# MCU.net
KiCad netlist of a schematic drawn in Altium Designer
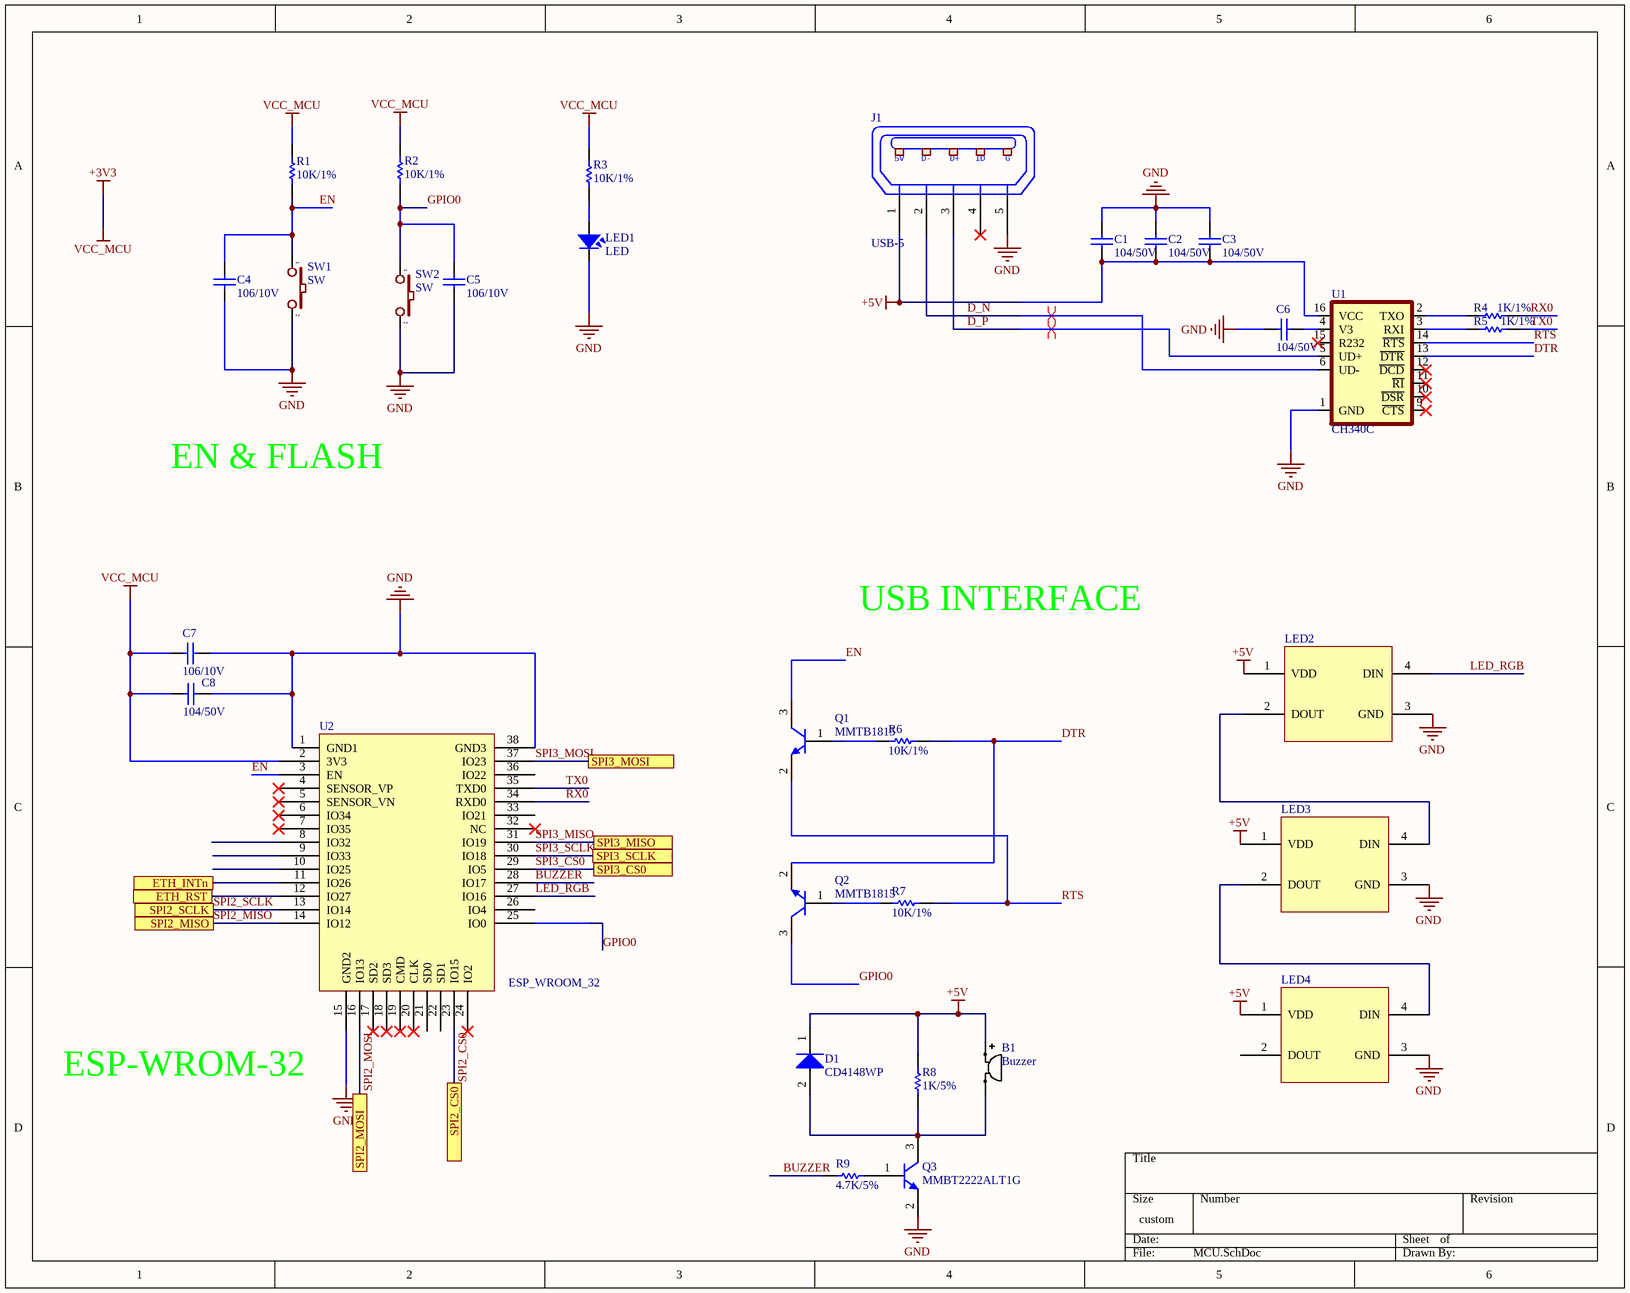
[diagram p0: MCU.SchDoc]

(export (version "E")
  (design (tool "Eeschema 10.0.6"))
  (components
    (comp (ref "B1")
      (value "Buzzer")
      (footprint "PS1240P02BT")
      (description "Audio Indicators & Alerts Round 12.2mmx6.5mm 4kHz Vin=3V")
      (fields
        (field (name "PARTNUMBER") "PS1240P02BT")
        (field (name "BSH PARTNUMBER") "New part")
        (field (name "CREATOR") "NamNHc")
      )
      (libsource (lib "library-SH") (part "BUZZER"))
    )
    (comp (ref "C1")
      (value "104/50V")
      (footprint "C0603-B")
      (description "100nF ±10% 50V X7R 0603 Multilayer Ceramic Capacitors MLCC - SMD/SMT RoHS")
      (fields
        (field (name "PARTNUMBER") "CL10B104KB8NNNC")
        (field (name "BSH PARTNUMBER") "C1591")
        (field (name "CREATOR") "Digo")
      )
      (libsource (lib "library-SH") (part "CAP"))
    )
    (comp (ref "C2")
      (value "104/50V")
      (footprint "C0603-B")
      (description "100nF ±10% 50V X7R 0603 Multilayer Ceramic Capacitors MLCC - SMD/SMT RoHS")
      (fields
        (field (name "PARTNUMBER") "CL10B104KB8NNNC")
        (field (name "BSH PARTNUMBER") "C1591")
        (field (name "CREATOR") "Digo")
      )
      (libsource (lib "library-SH") (part "CAP"))
    )
    (comp (ref "C3")
      (value "104/50V")
      (footprint "C0603-B")
      (description "100nF ±10% 50V X7R 0603 Multilayer Ceramic Capacitors MLCC - SMD/SMT RoHS")
      (fields
        (field (name "PARTNUMBER") "CL10B104KB8NNNC")
        (field (name "BSH PARTNUMBER") "C1591")
        (field (name "CREATOR") "Digo")
      )
      (libsource (lib "library-SH") (part "CAP"))
    )
    (comp (ref "C4")
      (value "106/10V")
      (footprint "C0603-B")
      (description "10uF ±10% 10V X5R 0603 Multilayer Ceramic Capacitors MLCC - SMD/SMT RoHS")
      (fields
        (field (name "PARTNUMBER") "CL10A106KP8NNNC")
        (field (name "BSH PARTNUMBER") "C19702")
        (field (name "CREATOR") "Digo")
      )
      (libsource (lib "library-SH") (part "CAP"))
    )
    (comp (ref "C5")
      (value "106/10V")
      (footprint "C0603-B")
      (description "10uF ±10% 10V X5R 0603 Multilayer Ceramic Capacitors MLCC - SMD/SMT RoHS")
      (fields
        (field (name "PARTNUMBER") "CL10A106KP8NNNC")
        (field (name "BSH PARTNUMBER") "C19702")
        (field (name "CREATOR") "Digo")
      )
      (libsource (lib "library-SH") (part "CAP"))
    )
    (comp (ref "C6")
      (value "104/50V")
      (footprint "C0603-B")
      (description "100nF ±10% 50V X7R 0603 Multilayer Ceramic Capacitors MLCC - SMD/SMT RoHS")
      (fields
        (field (name "PARTNUMBER") "CL10B104KB8NNNC")
        (field (name "BSH PARTNUMBER") "C1591")
        (field (name "CREATOR") "Digo")
      )
      (libsource (lib "library-SH") (part "CAP"))
    )
    (comp (ref "C7")
      (value "106/10V")
      (footprint "C0603-B")
      (description "10uF ±10% 10V X5R 0603 Multilayer Ceramic Capacitors MLCC - SMD/SMT RoHS")
      (fields
        (field (name "PARTNUMBER") "CL10A106KP8NNNC")
        (field (name "BSH PARTNUMBER") "C19702")
        (field (name "CREATOR") "Digo")
      )
      (libsource (lib "library-SH") (part "CAP"))
    )
    (comp (ref "C8")
      (value "104/50V")
      (footprint "C0603-B")
      (description "100nF ±10% 50V X7R 0603 Multilayer Ceramic Capacitors MLCC - SMD/SMT RoHS")
      (fields
        (field (name "PARTNUMBER") "CL10B104KB8NNNC")
        (field (name "BSH PARTNUMBER") "C1591")
        (field (name "CREATOR") "Digo")
      )
      (libsource (lib "library-SH") (part "CAP"))
    )
    (comp (ref "D1")
      (value "CD4148WP")
      (footprint "D1206-C")
      (description "DIO D1206 150mA 75V Switching Chip Diode")
      (fields (field (name "BSH PARTNUMBER") "D-CD4148WP") (field (name "CREATOR") "ChienNQ"))
      (libsource (lib "library-SH") (part "DIOT"))
    )
    (comp (ref "J1")
      (value "USB-5")
      (footprint "USB-M1")
      (fields
        (field (name "MANUFACTURER") "FCI")
        (field (name "MANUFACTURER PART NUMBER") "10118193-0001LF")
        (field (name ".CREATOR") "MM")
        (field (name ".CHECKED PCB") "RF")
        (field (name ".CHECKED SCH") "MM")
      )
      (libsource (lib "My Library") (part "USB-5"))
    )
    (comp (ref "LED1")
      (value "LED")
      (footprint "LED-0805-Red")
      (description "LED Single colour Green and Red")
      (libsource (lib "HS_Lib") (part "LED"))
    )
    (comp (ref "LED2")
      (value "RGB 4 Pin WS2812B")
      (footprint "WS2812B")
      (description "Intelligent control LED\r\nintegrated light source")
      (libsource (lib "My Library") (part "WS2812B"))
    )
    (comp (ref "LED3")
      (value "RGB 4 Pin WS2812B")
      (footprint "WS2812B")
      (description "Intelligent control LED\r\nintegrated light source")
      (libsource (lib "My Library") (part "WS2812B"))
    )
    (comp (ref "LED4")
      (value "RGB 4 Pin WS2812B")
      (footprint "WS2812B")
      (description "Intelligent control LED\r\nintegrated light source")
      (libsource (lib "My Library") (part "WS2812B"))
    )
    (comp (ref "Q1")
      (value "MMTB1815")
      (footprint "SOT23-321-C")
      (description "Transistor NPN SOT23 MMTB1815 Pitch_0.90 mm 2.92x2.00x1.11 mm")
      (fields (field (name "BSH PARTNUMBER") "Q-MMBT1815-TP") (field (name "CREATOR") "DucNTc"))
      (libsource (lib "library-SH") (part "Transistors-NPN"))
    )
    (comp (ref "Q2")
      (value "MMTB1815")
      (footprint "SOT23-321-C")
      (description "Transistor NPN SOT23 MMTB1815 Pitch_0.90 mm 2.92x2.00x1.11 mm")
      (fields (field (name "BSH PARTNUMBER") "Q-MMBT1815-TP") (field (name "CREATOR") "DucNTc"))
      (libsource (lib "library-SH") (part "Transistors-NPN"))
    )
    (comp (ref "Q3")
      (value "MMBT2222ALT1G")
      (footprint "SOT23-321-B")
      (description "Transistor NPN SOT23 MMBT2222A Pitch_0.90 mm 2.92x2.00x1.11mm")
      (fields (field (name "BSH PARTNUMBER") "Q-MMBT2222A") (field (name "CREATOR") "SmartDevice"))
      (libsource (lib "library-SH") (part "Transistors-NPN"))
    )
    (comp (ref "R1")
      (value "10K/1%")
      (footprint "R0603-B")
      (description "RES 0603 10K 1% 100mW")
      (fields
        (field (name "PARTNUMBER") "RC0603FR-0710KL")
        (field (name "BSH PARTNUMBER") "C98220")
        (field (name "CREATOR") "Digo")
      )
      (libsource (lib "library-SH") (part "RES"))
    )
    (comp (ref "R2")
      (value "10K/1%")
      (footprint "R0603-B")
      (description "RES 0603 10K 1% 100mW")
      (fields
        (field (name "PARTNUMBER") "RC0603FR-0710KL")
        (field (name "BSH PARTNUMBER") "C98220")
        (field (name "CREATOR") "Digo")
      )
      (libsource (lib "library-SH") (part "RES"))
    )
    (comp (ref "R3")
      (value "10K/1%")
      (footprint "R0603-B")
      (description "RES 0603 10K 1% 100mW")
      (fields
        (field (name "PARTNUMBER") "RC0603FR-0710KL")
        (field (name "BSH PARTNUMBER") "C98220")
        (field (name "CREATOR") "Digo")
      )
      (libsource (lib "library-SH") (part "RES"))
    )
    (comp (ref "R4")
      (value "1K/1%")
      (footprint "R0603-B")
      (description "RES 0603 1K 1% 100mW")
      (fields
        (field (name "PARTNUMBER") "RC0603FR-071KL")
        (field (name "BSH PARTNUMBER") "R-1k-0603-1")
        (field (name "CREATOR") "SmartDevice")
      )
      (libsource (lib "library-SH") (part "RES"))
    )
    (comp (ref "R5")
      (value "1K/1%")
      (footprint "R0603-B")
      (description "RES 0603 1K 1% 100mW")
      (fields
        (field (name "PARTNUMBER") "RC0603FR-071KL")
        (field (name "BSH PARTNUMBER") "R-1k-0603-1")
        (field (name "CREATOR") "SmartDevice")
      )
      (libsource (lib "library-SH") (part "RES"))
    )
    (comp (ref "R6")
      (value "10K/1%")
      (footprint "R0603-B")
      (description "RES 0603 10K 1% 100mW")
      (fields
        (field (name "PARTNUMBER") "RC0603FR-0710KL")
        (field (name "BSH PARTNUMBER") "C98220")
        (field (name "CREATOR") "Digo")
      )
      (libsource (lib "library-SH") (part "RES"))
    )
    (comp (ref "R7")
      (value "10K/1%")
      (footprint "R0603-B")
      (description "RES 0603 10K 1% 100mW")
      (fields
        (field (name "PARTNUMBER") "RC0603FR-0710KL")
        (field (name "BSH PARTNUMBER") "C98220")
        (field (name "CREATOR") "Digo")
      )
      (libsource (lib "library-SH") (part "RES"))
    )
    (comp (ref "R8")
      (value "1K/5%")
      (footprint "R0603-B")
      (description "RES 0603 1K 5% 100mW")
      (fields
        (field (name "PARTNUMBER") "RC0603JR-071KL")
        (field (name "BSH PARTNUMBER") "R-1K-0603-5")
        (field (name "CREATOR") "SmartDevice")
      )
      (libsource (lib "library-SH") (part "RES"))
    )
    (comp (ref "R9")
      (value "4.7K/5%")
      (footprint "R0603-B")
      (description "RES 0603 4K7 5% 100mW")
      (fields
        (field (name "PARTNUMBER") "RC0603JR-074K7L")
        (field (name "BSH PARTNUMBER") "R-4K7-0603-5")
        (field (name "CREATOR") "SmartDevice")
      )
      (libsource (lib "library-SH") (part "RES"))
    )
    (comp (ref "SW1")
      (value "SW")
      (footprint "SW2 - 3x4x2.5")
      (description "Switch button 2 pin")
      (libsource (lib "My Library") (part "SW2"))
    )
    (comp (ref "SW2")
      (value "SW")
      (footprint "SW2 - 3x4x2.5")
      (description "Switch button 2 pin")
      (libsource (lib "My Library") (part "SW2"))
    )
    (comp (ref "U1")
      (value "CH340C")
      (footprint "SO016")
      (description "USB to serial chip CH340")
      (fields (field (name "MF") "WCH"))
      (libsource (lib "HS_Lib") (part "CH340C"))
    )
    (comp (ref "U2")
      (value "ESP_WROOM_32")
      (footprint "ESP32_WROOM_32")
      (fields
        (field (name "MANUFACTURER") "Espressif Systems")
        (field (name "MANUFACTURER PART NUMBER") "ESP32-WROOM-32E(4MBHIGHTEMP)")
      )
      (libsource (lib "HS_Lib") (part "ESP_WROOM_32"))
    )
  )
  (nets
    (net (code "1") (name "+3V3") (class "Default")
      (node (ref "C7") (pin "2") (pinfunction "2_2") (pintype "passive"))
      (node (ref "C8") (pin "2") (pinfunction "2_2") (pintype "passive"))
      (node (ref "R1") (pin "2") (pinfunction "2_2") (pintype "passive"))
      (node (ref "R2") (pin "2") (pinfunction "2_2") (pintype "passive"))
      (node (ref "R3") (pin "2") (pinfunction "2_2") (pintype "passive"))
      (node (ref "U2") (pin "2") (pinfunction "3V3_2") (pintype "passive"))
    )
    (net (code "2") (name "+5V") (class "Default")
      (node (ref "B1") (pin "1") (pinfunction "1_1") (pintype "passive"))
      (node (ref "C1") (pin "1") (pinfunction "1_1") (pintype "passive"))
      (node (ref "C2") (pin "1") (pinfunction "1_1") (pintype "passive"))
      (node (ref "C3") (pin "1") (pinfunction "1_1") (pintype "passive"))
      (node (ref "D1") (pin "1") (pinfunction "K_1") (pintype "passive"))
      (node (ref "J1") (pin "1") (pinfunction "P1_1") (pintype "passive"))
      (node (ref "LED2") (pin "1") (pinfunction "VDD_1") (pintype "passive"))
      (node (ref "LED3") (pin "1") (pinfunction "VDD_1") (pintype "passive"))
      (node (ref "LED4") (pin "1") (pinfunction "VDD_1") (pintype "passive"))
      (node (ref "R8") (pin "2") (pinfunction "2_2") (pintype "passive"))
      (node (ref "U1") (pin "16") (pinfunction "VCC_16") (pintype "bidirectional"))
    )
    (net (code "3") (name "/BUZZER") (class "Default")
      (node (ref "R9") (pin "1") (pinfunction "1_1") (pintype "passive"))
      (node (ref "U2") (pin "28") (pinfunction "IO17_28") (pintype "passive"))
    )
    (net (code "4") (name "/DTR") (class "Default")
      (node (ref "Q2") (pin "2") (pinfunction "E_2") (pintype "passive"))
      (node (ref "R6") (pin "2") (pinfunction "2_2") (pintype "passive"))
      (node (ref "U1") (pin "13") (pinfunction "~{DTR}_13") (pintype "bidirectional"))
    )
    (net (code "5") (name "/D_N") (class "Default")
      (node (ref "J1") (pin "2") (pinfunction "P2_2") (pintype "passive"))
      (node (ref "U1") (pin "6") (pinfunction "UD-_6") (pintype "bidirectional"))
    )
    (net (code "6") (name "/D_P") (class "Default")
      (node (ref "J1") (pin "3") (pinfunction "P3_3") (pintype "passive"))
      (node (ref "U1") (pin "5") (pinfunction "UD+_5") (pintype "bidirectional"))
    )
    (net (code "7") (name "/EN") (class "Default")
      (node (ref "C4") (pin "2") (pinfunction "2_2") (pintype "passive"))
      (node (ref "Q1") (pin "3") (pinfunction "C_3") (pintype "passive"))
      (node (ref "R1") (pin "1") (pinfunction "1_1") (pintype "passive"))
      (node (ref "SW1") (pin "1") (pinfunction "1_1") (pintype "passive"))
      (node (ref "U2") (pin "3") (pinfunction "EN_3") (pintype "passive"))
    )
    (net (code "8") (name "/ETH_INTn") (class "Default")
      (node (ref "U2") (pin "11") (pinfunction "IO26_11") (pintype "passive"))
    )
    (net (code "9") (name "/ETH_RST") (class "Default")
      (node (ref "U2") (pin "12") (pinfunction "IO27_12") (pintype "passive"))
    )
    (net (code "10") (name "/GPIO0") (class "Default")
      (node (ref "C5") (pin "2") (pinfunction "2_2") (pintype "passive"))
      (node (ref "Q2") (pin "3") (pinfunction "C_3") (pintype "passive"))
      (node (ref "R2") (pin "1") (pinfunction "1_1") (pintype "passive"))
      (node (ref "SW2") (pin "1") (pinfunction "1_1") (pintype "passive"))
      (node (ref "U2") (pin "25") (pinfunction "IO0_25") (pintype "passive"))
    )
    (net (code "11") (name "/LED_RGB") (class "Default")
      (node (ref "LED2") (pin "4") (pinfunction "DIN_4") (pintype "passive"))
      (node (ref "U2") (pin "27") (pinfunction "IO16_27") (pintype "passive"))
    )
    (net (code "12") (name "/RTS") (class "Default")
      (node (ref "Q1") (pin "2") (pinfunction "E_2") (pintype "passive"))
      (node (ref "R7") (pin "2") (pinfunction "2_2") (pintype "passive"))
      (node (ref "U1") (pin "14") (pinfunction "~{RTS}_14") (pintype "bidirectional"))
    )
    (net (code "13") (name "/RX0") (class "Default")
      (node (ref "R4") (pin "2") (pinfunction "2_2") (pintype "passive"))
      (node (ref "U2") (pin "34") (pinfunction "RXD0_34") (pintype "passive"))
    )
    (net (code "14") (name "/SPI2_CS0") (class "Default")
      (node (ref "U2") (pin "23") (pinfunction "IO15_23") (pintype "passive"))
    )
    (net (code "15") (name "/SPI2_MISO") (class "Default")
      (node (ref "U2") (pin "14") (pinfunction "IO12_14") (pintype "passive"))
    )
    (net (code "16") (name "/SPI2_MOSI") (class "Default")
      (node (ref "U2") (pin "16") (pinfunction "IO13_16") (pintype "passive"))
    )
    (net (code "17") (name "/SPI2_SCLK") (class "Default")
      (node (ref "U2") (pin "13") (pinfunction "IO14_13") (pintype "passive"))
    )
    (net (code "18") (name "/SPI3_CS0") (class "Default")
      (node (ref "U2") (pin "29") (pinfunction "IO5_29") (pintype "passive"))
    )
    (net (code "19") (name "/SPI3_MISO") (class "Default")
      (node (ref "U2") (pin "31") (pinfunction "IO19_31") (pintype "passive"))
    )
    (net (code "20") (name "/SPI3_MOSI") (class "Default")
      (node (ref "U2") (pin "37") (pinfunction "IO23_37") (pintype "passive"))
    )
    (net (code "21") (name "/SPI3_SCLK") (class "Default")
      (node (ref "U2") (pin "30") (pinfunction "IO18_30") (pintype "passive"))
    )
    (net (code "22") (name "/TX0") (class "Default")
      (node (ref "R5") (pin "2") (pinfunction "2_2") (pintype "passive"))
      (node (ref "U2") (pin "35") (pinfunction "TXD0_35") (pintype "passive"))
    )
    (net (code "23") (name "GND") (class "Default")
      (node (ref "C1") (pin "2") (pinfunction "2_2") (pintype "passive"))
      (node (ref "C2") (pin "2") (pinfunction "2_2") (pintype "passive"))
      (node (ref "C3") (pin "2") (pinfunction "2_2") (pintype "passive"))
      (node (ref "C4") (pin "1") (pinfunction "1_1") (pintype "passive"))
      (node (ref "C5") (pin "1") (pinfunction "1_1") (pintype "passive"))
      (node (ref "C6") (pin "2") (pinfunction "2_2") (pintype "passive"))
      (node (ref "C7") (pin "1") (pinfunction "1_1") (pintype "passive"))
      (node (ref "C8") (pin "1") (pinfunction "1_1") (pintype "passive"))
      (node (ref "J1") (pin "5") (pinfunction "P5_5") (pintype "passive"))
      (node (ref "LED1") (pin "2") (pinfunction "2_2") (pintype "passive"))
      (node (ref "LED2") (pin "3") (pinfunction "GND_3") (pintype "passive"))
      (node (ref "LED3") (pin "3") (pinfunction "GND_3") (pintype "passive"))
      (node (ref "LED4") (pin "3") (pinfunction "GND_3") (pintype "passive"))
      (node (ref "Q3") (pin "2") (pinfunction "E_2") (pintype "passive"))
      (node (ref "SW1") (pin "2") (pinfunction "2_2") (pintype "passive"))
      (node (ref "SW2") (pin "2") (pinfunction "2_2") (pintype "passive"))
      (node (ref "U1") (pin "1") (pinfunction "GND_1") (pintype "bidirectional"))
      (node (ref "U2") (pin "1") (pinfunction "GND1_1") (pintype "power_in"))
      (node (ref "U2") (pin "15") (pinfunction "GND2_15") (pintype "passive"))
      (node (ref "U2") (pin "38") (pinfunction "GND3_38") (pintype "passive"))
    )
    (net (code "24") (name "Net-(D1-A)") (class "Default")
      (node (ref "B1") (pin "2") (pinfunction "2_2") (pintype "passive"))
      (node (ref "D1") (pin "2") (pinfunction "A_2") (pintype "passive"))
      (node (ref "Q3") (pin "3") (pinfunction "C_3") (pintype "passive"))
      (node (ref "R8") (pin "1") (pinfunction "1_1") (pintype "passive"))
    )
    (net (code "25") (name "Net-(LED1-Pad1)") (class "Default")
      (node (ref "LED1") (pin "1") (pinfunction "1_1") (pintype "passive"))
      (node (ref "R3") (pin "1") (pinfunction "1_1") (pintype "passive"))
    )
    (net (code "26") (name "Net-(LED2-DOUT)") (class "Default")
      (node (ref "LED2") (pin "2") (pinfunction "DOUT_2") (pintype "passive"))
      (node (ref "LED3") (pin "4") (pinfunction "DIN_4") (pintype "passive"))
    )
    (net (code "27") (name "Net-(LED3-DOUT)") (class "Default")
      (node (ref "LED3") (pin "2") (pinfunction "DOUT_2") (pintype "passive"))
      (node (ref "LED4") (pin "4") (pinfunction "DIN_4") (pintype "passive"))
    )
    (net (code "28") (name "Net-(Q1-B)") (class "Default")
      (node (ref "Q1") (pin "1") (pinfunction "B_1") (pintype "passive"))
      (node (ref "R6") (pin "1") (pinfunction "1_1") (pintype "passive"))
    )
    (net (code "29") (name "Net-(Q2-B)") (class "Default")
      (node (ref "Q2") (pin "1") (pinfunction "B_1") (pintype "passive"))
      (node (ref "R7") (pin "1") (pinfunction "1_1") (pintype "passive"))
    )
    (net (code "30") (name "Net-(Q3-B)") (class "Default")
      (node (ref "Q3") (pin "1") (pinfunction "B_1") (pintype "passive"))
      (node (ref "R9") (pin "2") (pinfunction "2_2") (pintype "passive"))
    )
    (net (code "31") (name "Net-(U1-RXI)") (class "Default")
      (node (ref "R5") (pin "1") (pinfunction "1_1") (pintype "passive"))
      (node (ref "U1") (pin "3") (pinfunction "RXI_3") (pintype "bidirectional"))
    )
    (net (code "32") (name "Net-(U1-TXO)") (class "Default")
      (node (ref "R4") (pin "1") (pinfunction "1_1") (pintype "passive"))
      (node (ref "U1") (pin "2") (pinfunction "TXO_2") (pintype "bidirectional"))
    )
    (net (code "33") (name "Net-(U1-V3)") (class "Default")
      (node (ref "C6") (pin "1") (pinfunction "1_1") (pintype "passive"))
      (node (ref "U1") (pin "4") (pinfunction "V3_4") (pintype "bidirectional"))
    )
    (net (code "34") (name "unconnected-(J1-P4-Pad4)") (class "Default")
      (node (ref "J1") (pin "4") (pinfunction "P4_4") (pintype "passive+no_connect"))
    )
    (net (code "35") (name "unconnected-(LED4-DOUT-Pad2)") (class "Default")
      (node (ref "LED4") (pin "2") (pinfunction "DOUT_2") (pintype "passive"))
    )
    (net (code "36") (name "unconnected-(U1-R232-Pad15)") (class "Default")
      (node (ref "U1") (pin "15") (pinfunction "R232_15") (pintype "bidirectional+no_connect"))
    )
    (net (code "37") (name "unconnected-(U1-~{CTS}-Pad9)") (class "Default")
      (node (ref "U1") (pin "9") (pinfunction "~{CTS}_9") (pintype "bidirectional+no_connect"))
    )
    (net (code "38") (name "unconnected-(U1-~{DCD}-Pad12)") (class "Default")
      (node (ref "U1") (pin "12") (pinfunction "~{DCD}_12") (pintype "bidirectional+no_connect"))
    )
    (net (code "39") (name "unconnected-(U1-~{DSR}-Pad10)") (class "Default")
      (node (ref "U1") (pin "10") (pinfunction "~{DSR}_10") (pintype "bidirectional+no_connect"))
    )
    (net (code "40") (name "unconnected-(U1-~{RI}-Pad11)") (class "Default")
      (node (ref "U1") (pin "11") (pinfunction "~{RI}_11") (pintype "bidirectional+no_connect"))
    )
    (net (code "41") (name "unconnected-(U2-CLK-Pad20)") (class "Default")
      (node (ref "U2") (pin "20") (pinfunction "CLK_20") (pintype "passive+no_connect"))
    )
    (net (code "42") (name "unconnected-(U2-CMD-Pad19)") (class "Default")
      (node (ref "U2") (pin "19") (pinfunction "CMD_19") (pintype "passive+no_connect"))
    )
    (net (code "43") (name "unconnected-(U2-IO2-Pad24)") (class "Default")
      (node (ref "U2") (pin "24") (pinfunction "IO2_24") (pintype "passive+no_connect"))
    )
    (net (code "44") (name "unconnected-(U2-IO4-Pad26)") (class "Default")
      (node (ref "U2") (pin "26") (pinfunction "IO4_26") (pintype "passive"))
    )
    (net (code "45") (name "unconnected-(U2-IO21-Pad33)") (class "Default")
      (node (ref "U2") (pin "33") (pinfunction "IO21_33") (pintype "passive"))
    )
    (net (code "46") (name "unconnected-(U2-IO22-Pad36)") (class "Default")
      (node (ref "U2") (pin "36") (pinfunction "IO22_36") (pintype "passive"))
    )
    (net (code "47") (name "unconnected-(U2-IO25-Pad10)") (class "Default")
      (node (ref "U2") (pin "10") (pinfunction "IO25_10") (pintype "passive"))
    )
    (net (code "48") (name "unconnected-(U2-IO32-Pad8)") (class "Default")
      (node (ref "U2") (pin "8") (pinfunction "IO32_8") (pintype "passive"))
    )
    (net (code "49") (name "unconnected-(U2-IO33-Pad9)") (class "Default")
      (node (ref "U2") (pin "9") (pinfunction "IO33_9") (pintype "passive"))
    )
    (net (code "50") (name "unconnected-(U2-IO34-Pad6)") (class "Default")
      (node (ref "U2") (pin "6") (pinfunction "IO34_6") (pintype "passive+no_connect"))
    )
    (net (code "51") (name "unconnected-(U2-IO35-Pad7)") (class "Default")
      (node (ref "U2") (pin "7") (pinfunction "IO35_7") (pintype "passive+no_connect"))
    )
    (net (code "52") (name "unconnected-(U2-NC-Pad32)") (class "Default")
      (node (ref "U2") (pin "32") (pinfunction "NC_32") (pintype "passive+no_connect"))
    )
    (net (code "53") (name "unconnected-(U2-SD0-Pad21)") (class "Default")
      (node (ref "U2") (pin "21") (pinfunction "SD0_21") (pintype "passive"))
    )
    (net (code "54") (name "unconnected-(U2-SD1-Pad22)") (class "Default")
      (node (ref "U2") (pin "22") (pinfunction "SD1_22") (pintype "passive"))
    )
    (net (code "55") (name "unconnected-(U2-SD2-Pad17)") (class "Default")
      (node (ref "U2") (pin "17") (pinfunction "SD2_17") (pintype "passive+no_connect"))
    )
    (net (code "56") (name "unconnected-(U2-SD3-Pad18)") (class "Default")
      (node (ref "U2") (pin "18") (pinfunction "SD3_18") (pintype "passive+no_connect"))
    )
    (net (code "57") (name "unconnected-(U2-SENSOR_VN-Pad5)") (class "Default")
      (node (ref "U2") (pin "5") (pinfunction "SENSOR_VN_5") (pintype "passive+no_connect"))
    )
    (net (code "58") (name "unconnected-(U2-SENSOR_VP-Pad4)") (class "Default")
      (node (ref "U2") (pin "4") (pinfunction "SENSOR_VP_4") (pintype "passive+no_connect"))
    )
  )
)
